# pocketbeagle_USB_hub_wifi.net
KiCad netlist of a schematic drawn in EAGLE
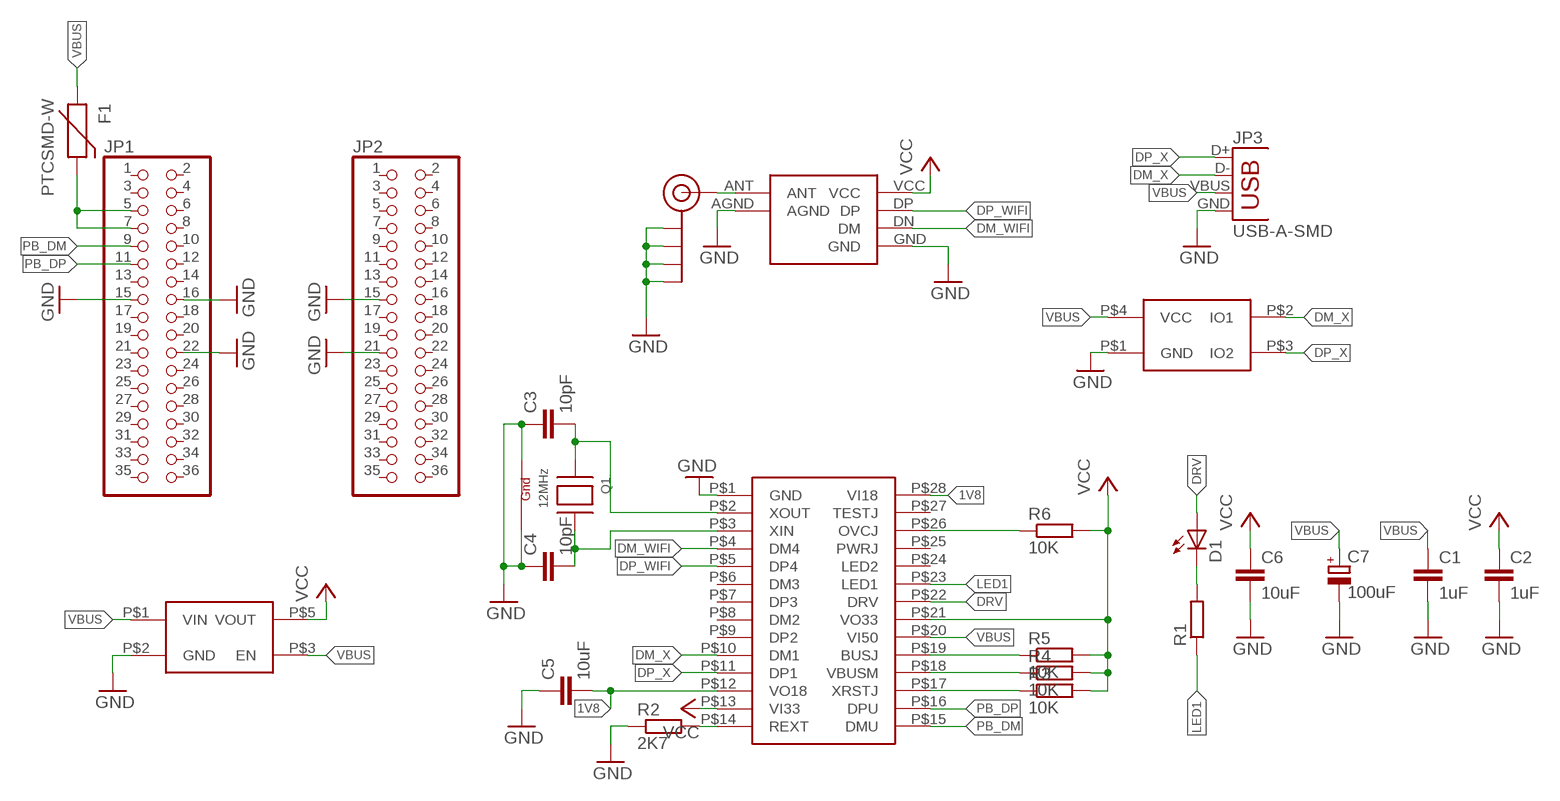
[diagram p0: schematic, sheet 1]

(export (version "E")
  (design (tool "Eeschema 10.0.6"))
  (components
    (comp (ref "C1")
      (value "1uF")
      (footprint "eagle-import:ONEFITSALL")
      (libsource (lib "eagle-import") (part "C-EUONEFITSALL"))
    )
    (comp (ref "C2")
      (value "1uF")
      (footprint "eagle-import:ONEFITSALL")
      (libsource (lib "eagle-import") (part "C-EUONEFITSALL"))
    )
    (comp (ref "C3")
      (value "10pF")
      (footprint "eagle-import:C0603")
      (libsource (lib "eagle-import") (part "C-EUC0603"))
    )
    (comp (ref "C4")
      (value "10pF")
      (footprint "eagle-import:C0603")
      (libsource (lib "eagle-import") (part "C-EUC0603"))
    )
    (comp (ref "C5")
      (value "10uF")
      (footprint "eagle-import:ONEFITSALL")
      (libsource (lib "eagle-import") (part "C-EUONEFITSALL"))
    )
    (comp (ref "C6")
      (value "10uF")
      (footprint "eagle-import:ONEFITSALL")
      (libsource (lib "eagle-import") (part "C-EUONEFITSALL"))
    )
    (comp (ref "C7")
      (value "100uF")
      (footprint "eagle-import:153CLV-0605")
      (libsource (lib "eagle-import") (part "CPOL-EU153CLV-0605"))
    )
    (comp (ref "D1")
      (value "LEDCHIP-LED0603")
      (footprint "eagle-import:CHIP-LED0603")
      (libsource (lib "eagle-import") (part "LEDCHIP-LED0603"))
    )
    (comp (ref "F1")
      (value "PTCSMD-W")
      (footprint "eagle-import:PTC-1206-WIDE")
      (libsource (lib "eagle-import") (part "PTCSMD-W"))
    )
    (comp (ref "J$1")
      (value "SMA_EDGE")
      (footprint "eagle-import:SMA-EDGE")
      (libsource (lib "eagle-import") (part "SMA_EDGE"))
    )
    (comp (ref "JP1")
      (value "PINHD-2X18")
      (footprint "eagle-import:2X18")
      (libsource (lib "eagle-import") (part "PINHD-2X18"))
    )
    (comp (ref "JP2")
      (value "PINHD-2X18")
      (footprint "eagle-import:2X18")
      (libsource (lib "eagle-import") (part "PINHD-2X18"))
    )
    (comp (ref "JP3")
      (value "USB-A-SMD")
      (footprint "eagle-import:USB-A-S-NOSILK-FEMALE")
      (libsource (lib "eagle-import") (part "USB-A-SMD"))
    )
    (comp (ref "Q1")
      (value "12MHz")
      (footprint "eagle-import:NX3225")
      (libsource (lib "eagle-import") (part "XTAL-4-3225"))
    )
    (comp (ref "R1")
      (value "R-EU_R0603")
      (footprint "eagle-import:R0603")
      (libsource (lib "eagle-import") (part "R-EU_R0603"))
    )
    (comp (ref "R2")
      (value "2K7")
      (footprint "eagle-import:R0603")
      (libsource (lib "eagle-import") (part "R-EU_R0603"))
    )
    (comp (ref "R3")
      (value "10K")
      (footprint "eagle-import:R0603")
      (libsource (lib "eagle-import") (part "R-EU_R0603"))
    )
    (comp (ref "R4")
      (value "10K")
      (footprint "eagle-import:R0603")
      (libsource (lib "eagle-import") (part "R-EU_R0603"))
    )
    (comp (ref "R5")
      (value "10K")
      (footprint "eagle-import:R0603")
      (libsource (lib "eagle-import") (part "R-EU_R0603"))
    )
    (comp (ref "R6")
      (value "10K")
      (footprint "eagle-import:R0603")
      (libsource (lib "eagle-import") (part "R-EU_R0603"))
    )
    (comp (ref "U$1")
      (value "RTL8188MODULE")
      (footprint "eagle-import:RTL8188")
      (libsource (lib "eagle-import") (part "RTL8188MODULE"))
    )
    (comp (ref "U$2")
      (value "FE1.1SSSOP28")
      (footprint "eagle-import:FE1.1S")
      (libsource (lib "eagle-import") (part "FE1.1SSSOP28"))
    )
    (comp (ref "U$3")
      (value "AP2112KAP2112K")
      (footprint "eagle-import:AP2112")
      (libsource (lib "eagle-import") (part "AP2112KAP2112K"))
    )
    (comp (ref "U$5")
      (value "PRTR5V0U2X")
      (footprint "eagle-import:PRTR5V0U2X")
      (libsource (lib "eagle-import") (part "PRTR5V0U2X"))
    )
  )
  (nets
    (net (code "1") (name "1V8") (class "Default")
      (node (ref "C5") (pin "P$2") (pinfunction "2_P$2") (pintype "passive"))
      (node (ref "U$2") (pin "P$12") (pinfunction "VO18_P$12") (pintype "bidirectional"))
      (node (ref "U$2") (pin "P$28") (pinfunction "VI18_P$28") (pintype "bidirectional"))
    )
    (net (code "2") (name "DM_WIFI") (class "Default")
      (node (ref "U$1") (pin "DN") (pinfunction "DM_DN") (pintype "bidirectional"))
      (node (ref "U$2") (pin "P$4") (pinfunction "DM4_P$4") (pintype "bidirectional"))
    )
    (net (code "3") (name "DM_X") (class "Default")
      (node (ref "JP3") (pin "D-") (pinfunction "D-_D-") (pintype "bidirectional"))
      (node (ref "U$2") (pin "P$10") (pinfunction "DM1_P$10") (pintype "bidirectional"))
      (node (ref "U$5") (pin "P$2") (pinfunction "IO1_P$2") (pintype "bidirectional"))
    )
    (net (code "4") (name "DP_WIFI") (class "Default")
      (node (ref "U$1") (pin "DP") (pinfunction "DP_DP") (pintype "bidirectional"))
      (node (ref "U$2") (pin "P$5") (pinfunction "DP4_P$5") (pintype "bidirectional"))
    )
    (net (code "5") (name "DP_X") (class "Default")
      (node (ref "JP3") (pin "D+") (pinfunction "D+_D+") (pintype "bidirectional"))
      (node (ref "U$2") (pin "P$11") (pinfunction "DP1_P$11") (pintype "bidirectional"))
      (node (ref "U$5") (pin "P$3") (pinfunction "IO2_P$3") (pintype "bidirectional"))
    )
    (net (code "6") (name "DRV") (class "Default")
      (node (ref "D1") (pin "A") (pinfunction "A_A") (pintype "passive"))
      (node (ref "U$2") (pin "P$22") (pinfunction "DRV_P$22") (pintype "bidirectional"))
    )
    (net (code "7") (name "GND") (class "Default")
      (node (ref "C1") (pin "P$2") (pinfunction "2_P$2") (pintype "passive"))
      (node (ref "C2") (pin "P$2") (pinfunction "2_P$2") (pintype "passive"))
      (node (ref "C3") (pin "1") (pinfunction "1_1") (pintype "passive"))
      (node (ref "C4") (pin "1") (pinfunction "1_1") (pintype "passive"))
      (node (ref "C5") (pin "P$1") (pinfunction "1_P$1") (pintype "passive"))
      (node (ref "C6") (pin "P$2") (pinfunction "2_P$2") (pintype "passive"))
      (node (ref "C7") (pin "-") (pinfunction "-_-") (pintype "passive"))
      (node (ref "J$1") (pin "GND@0") (pinfunction "GND_GND@0") (pintype "bidirectional"))
      (node (ref "J$1") (pin "GND@1") (pinfunction "GND_GND@1") (pintype "bidirectional"))
      (node (ref "J$1") (pin "GND@2") (pinfunction "GND_GND@2") (pintype "bidirectional"))
      (node (ref "J$1") (pin "GND@3") (pinfunction "GND_GND@3") (pintype "bidirectional"))
      (node (ref "JP1") (pin "15") (pinfunction "15_15") (pintype "passive"))
      (node (ref "JP1") (pin "16") (pinfunction "16_16") (pintype "passive"))
      (node (ref "JP1") (pin "22") (pinfunction "22_22") (pintype "passive"))
      (node (ref "JP2") (pin "15") (pinfunction "15_15") (pintype "passive"))
      (node (ref "JP2") (pin "21") (pinfunction "21_21") (pintype "passive"))
      (node (ref "JP3") (pin "GND") (pinfunction "GND_GND") (pintype "bidirectional"))
      (node (ref "Q1") (pin "2") (pinfunction "G2_2") (pintype "power_in"))
      (node (ref "Q1") (pin "4") (pinfunction "G1_4") (pintype "power_in"))
      (node (ref "R2") (pin "1") (pinfunction "1_1") (pintype "passive"))
      (node (ref "U$1") (pin "AGND") (pinfunction "AGND_AGND") (pintype "bidirectional"))
      (node (ref "U$1") (pin "GND") (pinfunction "GND_GND") (pintype "bidirectional"))
      (node (ref "U$2") (pin "P$1") (pinfunction "GND_P$1") (pintype "bidirectional"))
      (node (ref "U$3") (pin "P$2") (pinfunction "GND_P$2") (pintype "bidirectional"))
      (node (ref "U$5") (pin "P$1") (pinfunction "GND_P$1") (pintype "bidirectional"))
    )
    (net (code "8") (name "LED1") (class "Default")
      (node (ref "R1") (pin "1") (pinfunction "1_1") (pintype "passive"))
      (node (ref "U$2") (pin "P$23") (pinfunction "LED1_P$23") (pintype "bidirectional"))
    )
    (net (code "9") (name "Net-(D1-PadC)") (class "Default")
      (node (ref "D1") (pin "C") (pinfunction "C_C") (pintype "passive"))
      (node (ref "R1") (pin "2") (pinfunction "2_2") (pintype "passive"))
    )
    (net (code "10") (name "Net-(F1-Pad2)") (class "Default")
      (node (ref "F1") (pin "2") (pinfunction "2_2") (pintype "bidirectional"))
      (node (ref "JP1") (pin "5") (pinfunction "5_5") (pintype "passive"))
      (node (ref "JP1") (pin "7") (pinfunction "7_7") (pintype "passive"))
    )
    (net (code "11") (name "Net-(J$1-SIGNAL)") (class "Default")
      (node (ref "J$1") (pin "SIG") (pinfunction "SIGNAL_SIG") (pintype "bidirectional"))
      (node (ref "U$1") (pin "ANT") (pinfunction "ANT_ANT") (pintype "bidirectional"))
    )
    (net (code "12") (name "Net-(Q1-X1)") (class "Default")
      (node (ref "C3") (pin "2") (pinfunction "2_2") (pintype "passive"))
      (node (ref "Q1") (pin "1") (pinfunction "X1_1") (pintype "bidirectional"))
      (node (ref "U$2") (pin "P$2") (pinfunction "XOUT_P$2") (pintype "bidirectional"))
    )
    (net (code "13") (name "Net-(Q1-X2)") (class "Default")
      (node (ref "C4") (pin "2") (pinfunction "2_2") (pintype "passive"))
      (node (ref "Q1") (pin "3") (pinfunction "X2_3") (pintype "bidirectional"))
      (node (ref "U$2") (pin "P$3") (pinfunction "XIN_P$3") (pintype "bidirectional"))
    )
    (net (code "14") (name "Net-(U$2-BUSJ)") (class "Default")
      (node (ref "R5") (pin "1") (pinfunction "1_1") (pintype "passive"))
      (node (ref "U$2") (pin "P$19") (pinfunction "BUSJ_P$19") (pintype "bidirectional"))
    )
    (net (code "15") (name "Net-(U$2-OVCJ)") (class "Default")
      (node (ref "R6") (pin "1") (pinfunction "1_1") (pintype "passive"))
      (node (ref "U$2") (pin "P$26") (pinfunction "OVCJ_P$26") (pintype "bidirectional"))
    )
    (net (code "16") (name "Net-(U$2-REXT)") (class "Default")
      (node (ref "R2") (pin "2") (pinfunction "2_2") (pintype "passive"))
      (node (ref "U$2") (pin "P$14") (pinfunction "REXT_P$14") (pintype "bidirectional"))
    )
    (net (code "17") (name "Net-(U$2-VBUSM)") (class "Default")
      (node (ref "R4") (pin "1") (pinfunction "1_1") (pintype "passive"))
      (node (ref "U$2") (pin "P$18") (pinfunction "VBUSM_P$18") (pintype "bidirectional"))
    )
    (net (code "18") (name "Net-(U$2-XRSTJ)") (class "Default")
      (node (ref "R3") (pin "1") (pinfunction "1_1") (pintype "passive"))
      (node (ref "U$2") (pin "P$17") (pinfunction "XRSTJ_P$17") (pintype "bidirectional"))
    )
    (net (code "19") (name "PB_DM") (class "Default")
      (node (ref "JP1") (pin "9") (pinfunction "9_9") (pintype "passive"))
      (node (ref "U$2") (pin "P$15") (pinfunction "DMU_P$15") (pintype "bidirectional"))
    )
    (net (code "20") (name "PB_DP") (class "Default")
      (node (ref "JP1") (pin "11") (pinfunction "11_11") (pintype "passive"))
      (node (ref "U$2") (pin "P$16") (pinfunction "DPU_P$16") (pintype "bidirectional"))
    )
    (net (code "21") (name "VBUS") (class "Default")
      (node (ref "C1") (pin "P$1") (pinfunction "1_P$1") (pintype "passive"))
      (node (ref "C7") (pin "+") (pinfunction "+_+") (pintype "passive"))
      (node (ref "F1") (pin "1") (pinfunction "1_1") (pintype "bidirectional"))
      (node (ref "JP3") (pin "VBUS") (pinfunction "VBUS_VBUS") (pintype "bidirectional"))
      (node (ref "U$2") (pin "P$20") (pinfunction "VI50_P$20") (pintype "bidirectional"))
      (node (ref "U$3") (pin "P$1") (pinfunction "VIN_P$1") (pintype "bidirectional"))
      (node (ref "U$3") (pin "P$3") (pinfunction "EN_P$3") (pintype "bidirectional"))
      (node (ref "U$5") (pin "P$4") (pinfunction "VCC_P$4") (pintype "bidirectional"))
    )
    (net (code "22") (name "VCC") (class "Default")
      (node (ref "C2") (pin "P$1") (pinfunction "1_P$1") (pintype "passive"))
      (node (ref "C6") (pin "P$1") (pinfunction "1_P$1") (pintype "passive"))
      (node (ref "R3") (pin "2") (pinfunction "2_2") (pintype "passive"))
      (node (ref "R4") (pin "2") (pinfunction "2_2") (pintype "passive"))
      (node (ref "R5") (pin "2") (pinfunction "2_2") (pintype "passive"))
      (node (ref "R6") (pin "2") (pinfunction "2_2") (pintype "passive"))
      (node (ref "U$1") (pin "VCC") (pinfunction "VCC_VCC") (pintype "bidirectional"))
      (node (ref "U$2") (pin "P$13") (pinfunction "VI33_P$13") (pintype "bidirectional"))
      (node (ref "U$2") (pin "P$21") (pinfunction "VO33_P$21") (pintype "bidirectional"))
      (node (ref "U$3") (pin "P$5") (pinfunction "VOUT_P$5") (pintype "bidirectional"))
    )
    (net (code "23") (name "unconnected-(JP1-Pad1)") (class "Default")
      (node (ref "JP1") (pin "1") (pinfunction "1_1") (pintype "passive"))
    )
    (net (code "24") (name "unconnected-(JP1-Pad2)") (class "Default")
      (node (ref "JP1") (pin "2") (pinfunction "2_2") (pintype "passive"))
    )
    (net (code "25") (name "unconnected-(JP1-Pad3)") (class "Default")
      (node (ref "JP1") (pin "3") (pinfunction "3_3") (pintype "passive"))
    )
    (net (code "26") (name "unconnected-(JP1-Pad4)") (class "Default")
      (node (ref "JP1") (pin "4") (pinfunction "4_4") (pintype "passive"))
    )
    (net (code "27") (name "unconnected-(JP1-Pad6)") (class "Default")
      (node (ref "JP1") (pin "6") (pinfunction "6_6") (pintype "passive"))
    )
    (net (code "28") (name "unconnected-(JP1-Pad8)") (class "Default")
      (node (ref "JP1") (pin "8") (pinfunction "8_8") (pintype "passive"))
    )
    (net (code "29") (name "unconnected-(JP1-Pad10)") (class "Default")
      (node (ref "JP1") (pin "10") (pinfunction "10_10") (pintype "passive"))
    )
    (net (code "30") (name "unconnected-(JP1-Pad12)") (class "Default")
      (node (ref "JP1") (pin "12") (pinfunction "12_12") (pintype "passive"))
    )
    (net (code "31") (name "unconnected-(JP1-Pad13)") (class "Default")
      (node (ref "JP1") (pin "13") (pinfunction "13_13") (pintype "passive"))
    )
    (net (code "32") (name "unconnected-(JP1-Pad14)") (class "Default")
      (node (ref "JP1") (pin "14") (pinfunction "14_14") (pintype "passive"))
    )
    (net (code "33") (name "unconnected-(JP1-Pad17)") (class "Default")
      (node (ref "JP1") (pin "17") (pinfunction "17_17") (pintype "passive"))
    )
    (net (code "34") (name "unconnected-(JP1-Pad18)") (class "Default")
      (node (ref "JP1") (pin "18") (pinfunction "18_18") (pintype "passive"))
    )
    (net (code "35") (name "unconnected-(JP1-Pad19)") (class "Default")
      (node (ref "JP1") (pin "19") (pinfunction "19_19") (pintype "passive"))
    )
    (net (code "36") (name "unconnected-(JP1-Pad20)") (class "Default")
      (node (ref "JP1") (pin "20") (pinfunction "20_20") (pintype "passive"))
    )
    (net (code "37") (name "unconnected-(JP1-Pad21)") (class "Default")
      (node (ref "JP1") (pin "21") (pinfunction "21_21") (pintype "passive"))
    )
    (net (code "38") (name "unconnected-(JP1-Pad23)") (class "Default")
      (node (ref "JP1") (pin "23") (pinfunction "23_23") (pintype "passive"))
    )
    (net (code "39") (name "unconnected-(JP1-Pad24)") (class "Default")
      (node (ref "JP1") (pin "24") (pinfunction "24_24") (pintype "passive"))
    )
    (net (code "40") (name "unconnected-(JP1-Pad25)") (class "Default")
      (node (ref "JP1") (pin "25") (pinfunction "25_25") (pintype "passive"))
    )
    (net (code "41") (name "unconnected-(JP1-Pad26)") (class "Default")
      (node (ref "JP1") (pin "26") (pinfunction "26_26") (pintype "passive"))
    )
    (net (code "42") (name "unconnected-(JP1-Pad27)") (class "Default")
      (node (ref "JP1") (pin "27") (pinfunction "27_27") (pintype "passive"))
    )
    (net (code "43") (name "unconnected-(JP1-Pad28)") (class "Default")
      (node (ref "JP1") (pin "28") (pinfunction "28_28") (pintype "passive"))
    )
    (net (code "44") (name "unconnected-(JP1-Pad29)") (class "Default")
      (node (ref "JP1") (pin "29") (pinfunction "29_29") (pintype "passive"))
    )
    (net (code "45") (name "unconnected-(JP1-Pad30)") (class "Default")
      (node (ref "JP1") (pin "30") (pinfunction "30_30") (pintype "passive"))
    )
    (net (code "46") (name "unconnected-(JP1-Pad31)") (class "Default")
      (node (ref "JP1") (pin "31") (pinfunction "31_31") (pintype "passive"))
    )
    (net (code "47") (name "unconnected-(JP1-Pad32)") (class "Default")
      (node (ref "JP1") (pin "32") (pinfunction "32_32") (pintype "passive"))
    )
    (net (code "48") (name "unconnected-(JP1-Pad33)") (class "Default")
      (node (ref "JP1") (pin "33") (pinfunction "33_33") (pintype "passive"))
    )
    (net (code "49") (name "unconnected-(JP1-Pad34)") (class "Default")
      (node (ref "JP1") (pin "34") (pinfunction "34_34") (pintype "passive"))
    )
    (net (code "50") (name "unconnected-(JP1-Pad35)") (class "Default")
      (node (ref "JP1") (pin "35") (pinfunction "35_35") (pintype "passive"))
    )
    (net (code "51") (name "unconnected-(JP1-Pad36)") (class "Default")
      (node (ref "JP1") (pin "36") (pinfunction "36_36") (pintype "passive"))
    )
    (net (code "52") (name "unconnected-(JP2-Pad1)") (class "Default")
      (node (ref "JP2") (pin "1") (pinfunction "1_1") (pintype "passive"))
    )
    (net (code "53") (name "unconnected-(JP2-Pad2)") (class "Default")
      (node (ref "JP2") (pin "2") (pinfunction "2_2") (pintype "passive"))
    )
    (net (code "54") (name "unconnected-(JP2-Pad3)") (class "Default")
      (node (ref "JP2") (pin "3") (pinfunction "3_3") (pintype "passive"))
    )
    (net (code "55") (name "unconnected-(JP2-Pad4)") (class "Default")
      (node (ref "JP2") (pin "4") (pinfunction "4_4") (pintype "passive"))
    )
    (net (code "56") (name "unconnected-(JP2-Pad5)") (class "Default")
      (node (ref "JP2") (pin "5") (pinfunction "5_5") (pintype "passive"))
    )
    (net (code "57") (name "unconnected-(JP2-Pad6)") (class "Default")
      (node (ref "JP2") (pin "6") (pinfunction "6_6") (pintype "passive"))
    )
    (net (code "58") (name "unconnected-(JP2-Pad7)") (class "Default")
      (node (ref "JP2") (pin "7") (pinfunction "7_7") (pintype "passive"))
    )
    (net (code "59") (name "unconnected-(JP2-Pad8)") (class "Default")
      (node (ref "JP2") (pin "8") (pinfunction "8_8") (pintype "passive"))
    )
    (net (code "60") (name "unconnected-(JP2-Pad9)") (class "Default")
      (node (ref "JP2") (pin "9") (pinfunction "9_9") (pintype "passive"))
    )
    (net (code "61") (name "unconnected-(JP2-Pad10)") (class "Default")
      (node (ref "JP2") (pin "10") (pinfunction "10_10") (pintype "passive"))
    )
    (net (code "62") (name "unconnected-(JP2-Pad11)") (class "Default")
      (node (ref "JP2") (pin "11") (pinfunction "11_11") (pintype "passive"))
    )
    (net (code "63") (name "unconnected-(JP2-Pad12)") (class "Default")
      (node (ref "JP2") (pin "12") (pinfunction "12_12") (pintype "passive"))
    )
    (net (code "64") (name "unconnected-(JP2-Pad13)") (class "Default")
      (node (ref "JP2") (pin "13") (pinfunction "13_13") (pintype "passive"))
    )
    (net (code "65") (name "unconnected-(JP2-Pad14)") (class "Default")
      (node (ref "JP2") (pin "14") (pinfunction "14_14") (pintype "passive"))
    )
    (net (code "66") (name "unconnected-(JP2-Pad16)") (class "Default")
      (node (ref "JP2") (pin "16") (pinfunction "16_16") (pintype "passive"))
    )
    (net (code "67") (name "unconnected-(JP2-Pad17)") (class "Default")
      (node (ref "JP2") (pin "17") (pinfunction "17_17") (pintype "passive"))
    )
    (net (code "68") (name "unconnected-(JP2-Pad18)") (class "Default")
      (node (ref "JP2") (pin "18") (pinfunction "18_18") (pintype "passive"))
    )
    (net (code "69") (name "unconnected-(JP2-Pad19)") (class "Default")
      (node (ref "JP2") (pin "19") (pinfunction "19_19") (pintype "passive"))
    )
    (net (code "70") (name "unconnected-(JP2-Pad20)") (class "Default")
      (node (ref "JP2") (pin "20") (pinfunction "20_20") (pintype "passive"))
    )
    (net (code "71") (name "unconnected-(JP2-Pad22)") (class "Default")
      (node (ref "JP2") (pin "22") (pinfunction "22_22") (pintype "passive"))
    )
    (net (code "72") (name "unconnected-(JP2-Pad23)") (class "Default")
      (node (ref "JP2") (pin "23") (pinfunction "23_23") (pintype "passive"))
    )
    (net (code "73") (name "unconnected-(JP2-Pad24)") (class "Default")
      (node (ref "JP2") (pin "24") (pinfunction "24_24") (pintype "passive"))
    )
    (net (code "74") (name "unconnected-(JP2-Pad25)") (class "Default")
      (node (ref "JP2") (pin "25") (pinfunction "25_25") (pintype "passive"))
    )
    (net (code "75") (name "unconnected-(JP2-Pad26)") (class "Default")
      (node (ref "JP2") (pin "26") (pinfunction "26_26") (pintype "passive"))
    )
    (net (code "76") (name "unconnected-(JP2-Pad27)") (class "Default")
      (node (ref "JP2") (pin "27") (pinfunction "27_27") (pintype "passive"))
    )
    (net (code "77") (name "unconnected-(JP2-Pad28)") (class "Default")
      (node (ref "JP2") (pin "28") (pinfunction "28_28") (pintype "passive"))
    )
    (net (code "78") (name "unconnected-(JP2-Pad29)") (class "Default")
      (node (ref "JP2") (pin "29") (pinfunction "29_29") (pintype "passive"))
    )
    (net (code "79") (name "unconnected-(JP2-Pad30)") (class "Default")
      (node (ref "JP2") (pin "30") (pinfunction "30_30") (pintype "passive"))
    )
    (net (code "80") (name "unconnected-(JP2-Pad31)") (class "Default")
      (node (ref "JP2") (pin "31") (pinfunction "31_31") (pintype "passive"))
    )
    (net (code "81") (name "unconnected-(JP2-Pad32)") (class "Default")
      (node (ref "JP2") (pin "32") (pinfunction "32_32") (pintype "passive"))
    )
    (net (code "82") (name "unconnected-(JP2-Pad33)") (class "Default")
      (node (ref "JP2") (pin "33") (pinfunction "33_33") (pintype "passive"))
    )
    (net (code "83") (name "unconnected-(JP2-Pad34)") (class "Default")
      (node (ref "JP2") (pin "34") (pinfunction "34_34") (pintype "passive"))
    )
    (net (code "84") (name "unconnected-(JP2-Pad35)") (class "Default")
      (node (ref "JP2") (pin "35") (pinfunction "35_35") (pintype "passive"))
    )
    (net (code "85") (name "unconnected-(JP2-Pad36)") (class "Default")
      (node (ref "JP2") (pin "36") (pinfunction "36_36") (pintype "passive"))
    )
    (net (code "86") (name "unconnected-(U$2-DM2-PadP$8)") (class "Default")
      (node (ref "U$2") (pin "P$8") (pinfunction "DM2_P$8") (pintype "bidirectional"))
    )
    (net (code "87") (name "unconnected-(U$2-DM3-PadP$6)") (class "Default")
      (node (ref "U$2") (pin "P$6") (pinfunction "DM3_P$6") (pintype "bidirectional"))
    )
    (net (code "88") (name "unconnected-(U$2-DP2-PadP$9)") (class "Default")
      (node (ref "U$2") (pin "P$9") (pinfunction "DP2_P$9") (pintype "bidirectional"))
    )
    (net (code "89") (name "unconnected-(U$2-DP3-PadP$7)") (class "Default")
      (node (ref "U$2") (pin "P$7") (pinfunction "DP3_P$7") (pintype "bidirectional"))
    )
    (net (code "90") (name "unconnected-(U$2-LED2-PadP$24)") (class "Default")
      (node (ref "U$2") (pin "P$24") (pinfunction "LED2_P$24") (pintype "bidirectional"))
    )
    (net (code "91") (name "unconnected-(U$2-PWRJ-PadP$25)") (class "Default")
      (node (ref "U$2") (pin "P$25") (pinfunction "PWRJ_P$25") (pintype "bidirectional"))
    )
    (net (code "92") (name "unconnected-(U$2-TESTJ-PadP$27)") (class "Default")
      (node (ref "U$2") (pin "P$27") (pinfunction "TESTJ_P$27") (pintype "bidirectional"))
    )
  )
)
